# DFROBOT_DS3231M.net
KiCad netlist of a schematic drawn in EAGLE
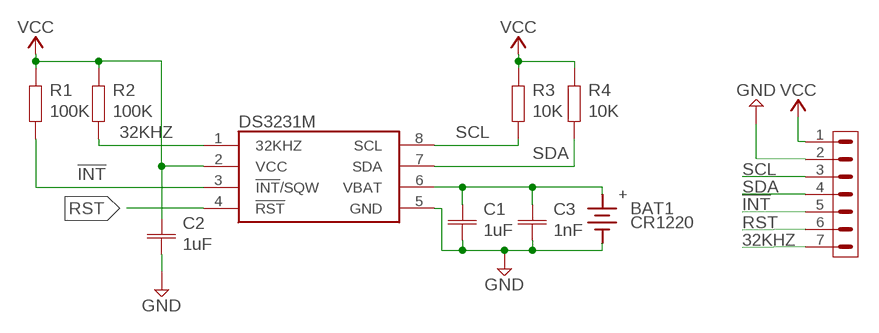
[diagram p0: schematic, sheet 1]

(export (version "E")
  (design (tool "Eeschema 10.0.6"))
  (components
    (comp (ref "BAT1")
      (value "CR1220")
      (footprint "eagle-import:S8411-45R")
      (libsource (lib "eagle-import") (part "S8411-45R"))
    )
    (comp (ref "C1")
      (value "1uF")
      (footprint "eagle-import:CAPC1005X60")
      (libsource (lib "eagle-import") (part "CCHIP-0402(1005-METRIC)_"))
    )
    (comp (ref "C2")
      (value "1uF")
      (footprint "eagle-import:CAPC1005X60")
      (libsource (lib "eagle-import") (part "CCHIP-0402(1005-METRIC)_"))
    )
    (comp (ref "C3")
      (value "1nF")
      (footprint "eagle-import:CAPC1005X60")
      (libsource (lib "eagle-import") (part "CCHIP-0402(1005-METRIC)_"))
    )
    (comp (ref "DS3231M")
      (value "DS3231MZ+")
      (footprint "eagle-import:SOIC127P600X175-8N")
      (fields (field (name "MOUSER_PART_NUMBER") "700-DS3231MZ+"))
      (libsource (lib "eagle-import") (part "DS3231MZ+"))
    )
    (comp (ref "JP1")
      (value "PINHD-1X7")
      (footprint "eagle-import:DS3231M_HEADER")
      (libsource (lib "eagle-import") (part "DS3231M_HEADERFEMALE"))
    )
    (comp (ref "R1")
      (value "100K")
      (footprint "eagle-import:RESC1005X40")
      (libsource (lib "eagle-import") (part "RCHIP-0402(1005-METRIC)_"))
    )
    (comp (ref "R2")
      (value "100K")
      (footprint "eagle-import:RESC1005X40")
      (libsource (lib "eagle-import") (part "RCHIP-0402(1005-METRIC)_"))
    )
    (comp (ref "R3")
      (value "10K")
      (footprint "eagle-import:RESC1005X40")
      (libsource (lib "eagle-import") (part "RCHIP-0402(1005-METRIC)_"))
    )
    (comp (ref "R4")
      (value "10K")
      (footprint "eagle-import:RESC1005X40")
      (libsource (lib "eagle-import") (part "RCHIP-0402(1005-METRIC)_"))
    )
  )
  (nets
    (net (code "1") (name "/32KHZ") (class "Default")
      (node (ref "DS3231M") (pin "1") (pinfunction "32KHZ_1") (pintype "output"))
      (node (ref "JP1") (pin "7") (pinfunction "7_7") (pintype "output"))
      (node (ref "R2") (pin "2") (pinfunction "2_2") (pintype "passive"))
    )
    (net (code "2") (name "/SCL") (class "Default")
      (node (ref "DS3231M") (pin "8") (pinfunction "SCL_8") (pintype "bidirectional"))
      (node (ref "JP1") (pin "3") (pinfunction "3_3") (pintype "bidirectional"))
      (node (ref "R3") (pin "2") (pinfunction "2_2") (pintype "passive"))
    )
    (net (code "3") (name "/SDA") (class "Default")
      (node (ref "DS3231M") (pin "7") (pinfunction "SDA_7") (pintype "bidirectional"))
      (node (ref "JP1") (pin "4") (pinfunction "4_4") (pintype "bidirectional"))
      (node (ref "R4") (pin "2") (pinfunction "2_2") (pintype "passive"))
    )
    (net (code "4") (name "/~{INT}") (class "Default")
      (node (ref "DS3231M") (pin "3") (pinfunction "~{INT}/SQW_3") (pintype "output"))
      (node (ref "JP1") (pin "5") (pinfunction "5_5") (pintype "output"))
      (node (ref "R1") (pin "2") (pinfunction "2_2") (pintype "passive"))
    )
    (net (code "5") (name "GND") (class "Default")
      (node (ref "BAT1") (pin "1") (pinfunction "-_1") (pintype "power_in"))
      (node (ref "C1") (pin "2") (pinfunction "2_2") (pintype "passive"))
      (node (ref "C2") (pin "2") (pinfunction "2_2") (pintype "passive"))
      (node (ref "C3") (pin "2") (pinfunction "2_2") (pintype "passive"))
      (node (ref "DS3231M") (pin "5") (pinfunction "GND_5") (pintype "power_in"))
      (node (ref "JP1") (pin "2") (pinfunction "2_2") (pintype "power_in"))
    )
    (net (code "6") (name "Net-(BAT1-+)") (class "Default")
      (node (ref "BAT1") (pin "2") (pinfunction "+_2") (pintype "power_in"))
      (node (ref "C1") (pin "1") (pinfunction "1_1") (pintype "passive"))
      (node (ref "C3") (pin "1") (pinfunction "1_1") (pintype "passive"))
      (node (ref "DS3231M") (pin "6") (pinfunction "VBAT_6") (pintype "power_in"))
    )
    (net (code "7") (name "RST") (class "Default")
      (node (ref "DS3231M") (pin "4") (pinfunction "~{RST}_4") (pintype "input"))
      (node (ref "JP1") (pin "6") (pinfunction "6_6") (pintype "input"))
    )
    (net (code "8") (name "VCC") (class "Default")
      (node (ref "C2") (pin "1") (pinfunction "1_1") (pintype "passive"))
      (node (ref "DS3231M") (pin "2") (pinfunction "VCC_2") (pintype "power_in"))
      (node (ref "JP1") (pin "1") (pinfunction "1_1") (pintype "power_in"))
      (node (ref "R1") (pin "1") (pinfunction "1_1") (pintype "passive"))
      (node (ref "R2") (pin "1") (pinfunction "1_1") (pintype "passive"))
      (node (ref "R3") (pin "1") (pinfunction "1_1") (pintype "passive"))
      (node (ref "R4") (pin "1") (pinfunction "1_1") (pintype "passive"))
    )
  )
)
